# module.net
KiCad netlist of a schematic drawn in EAGLE
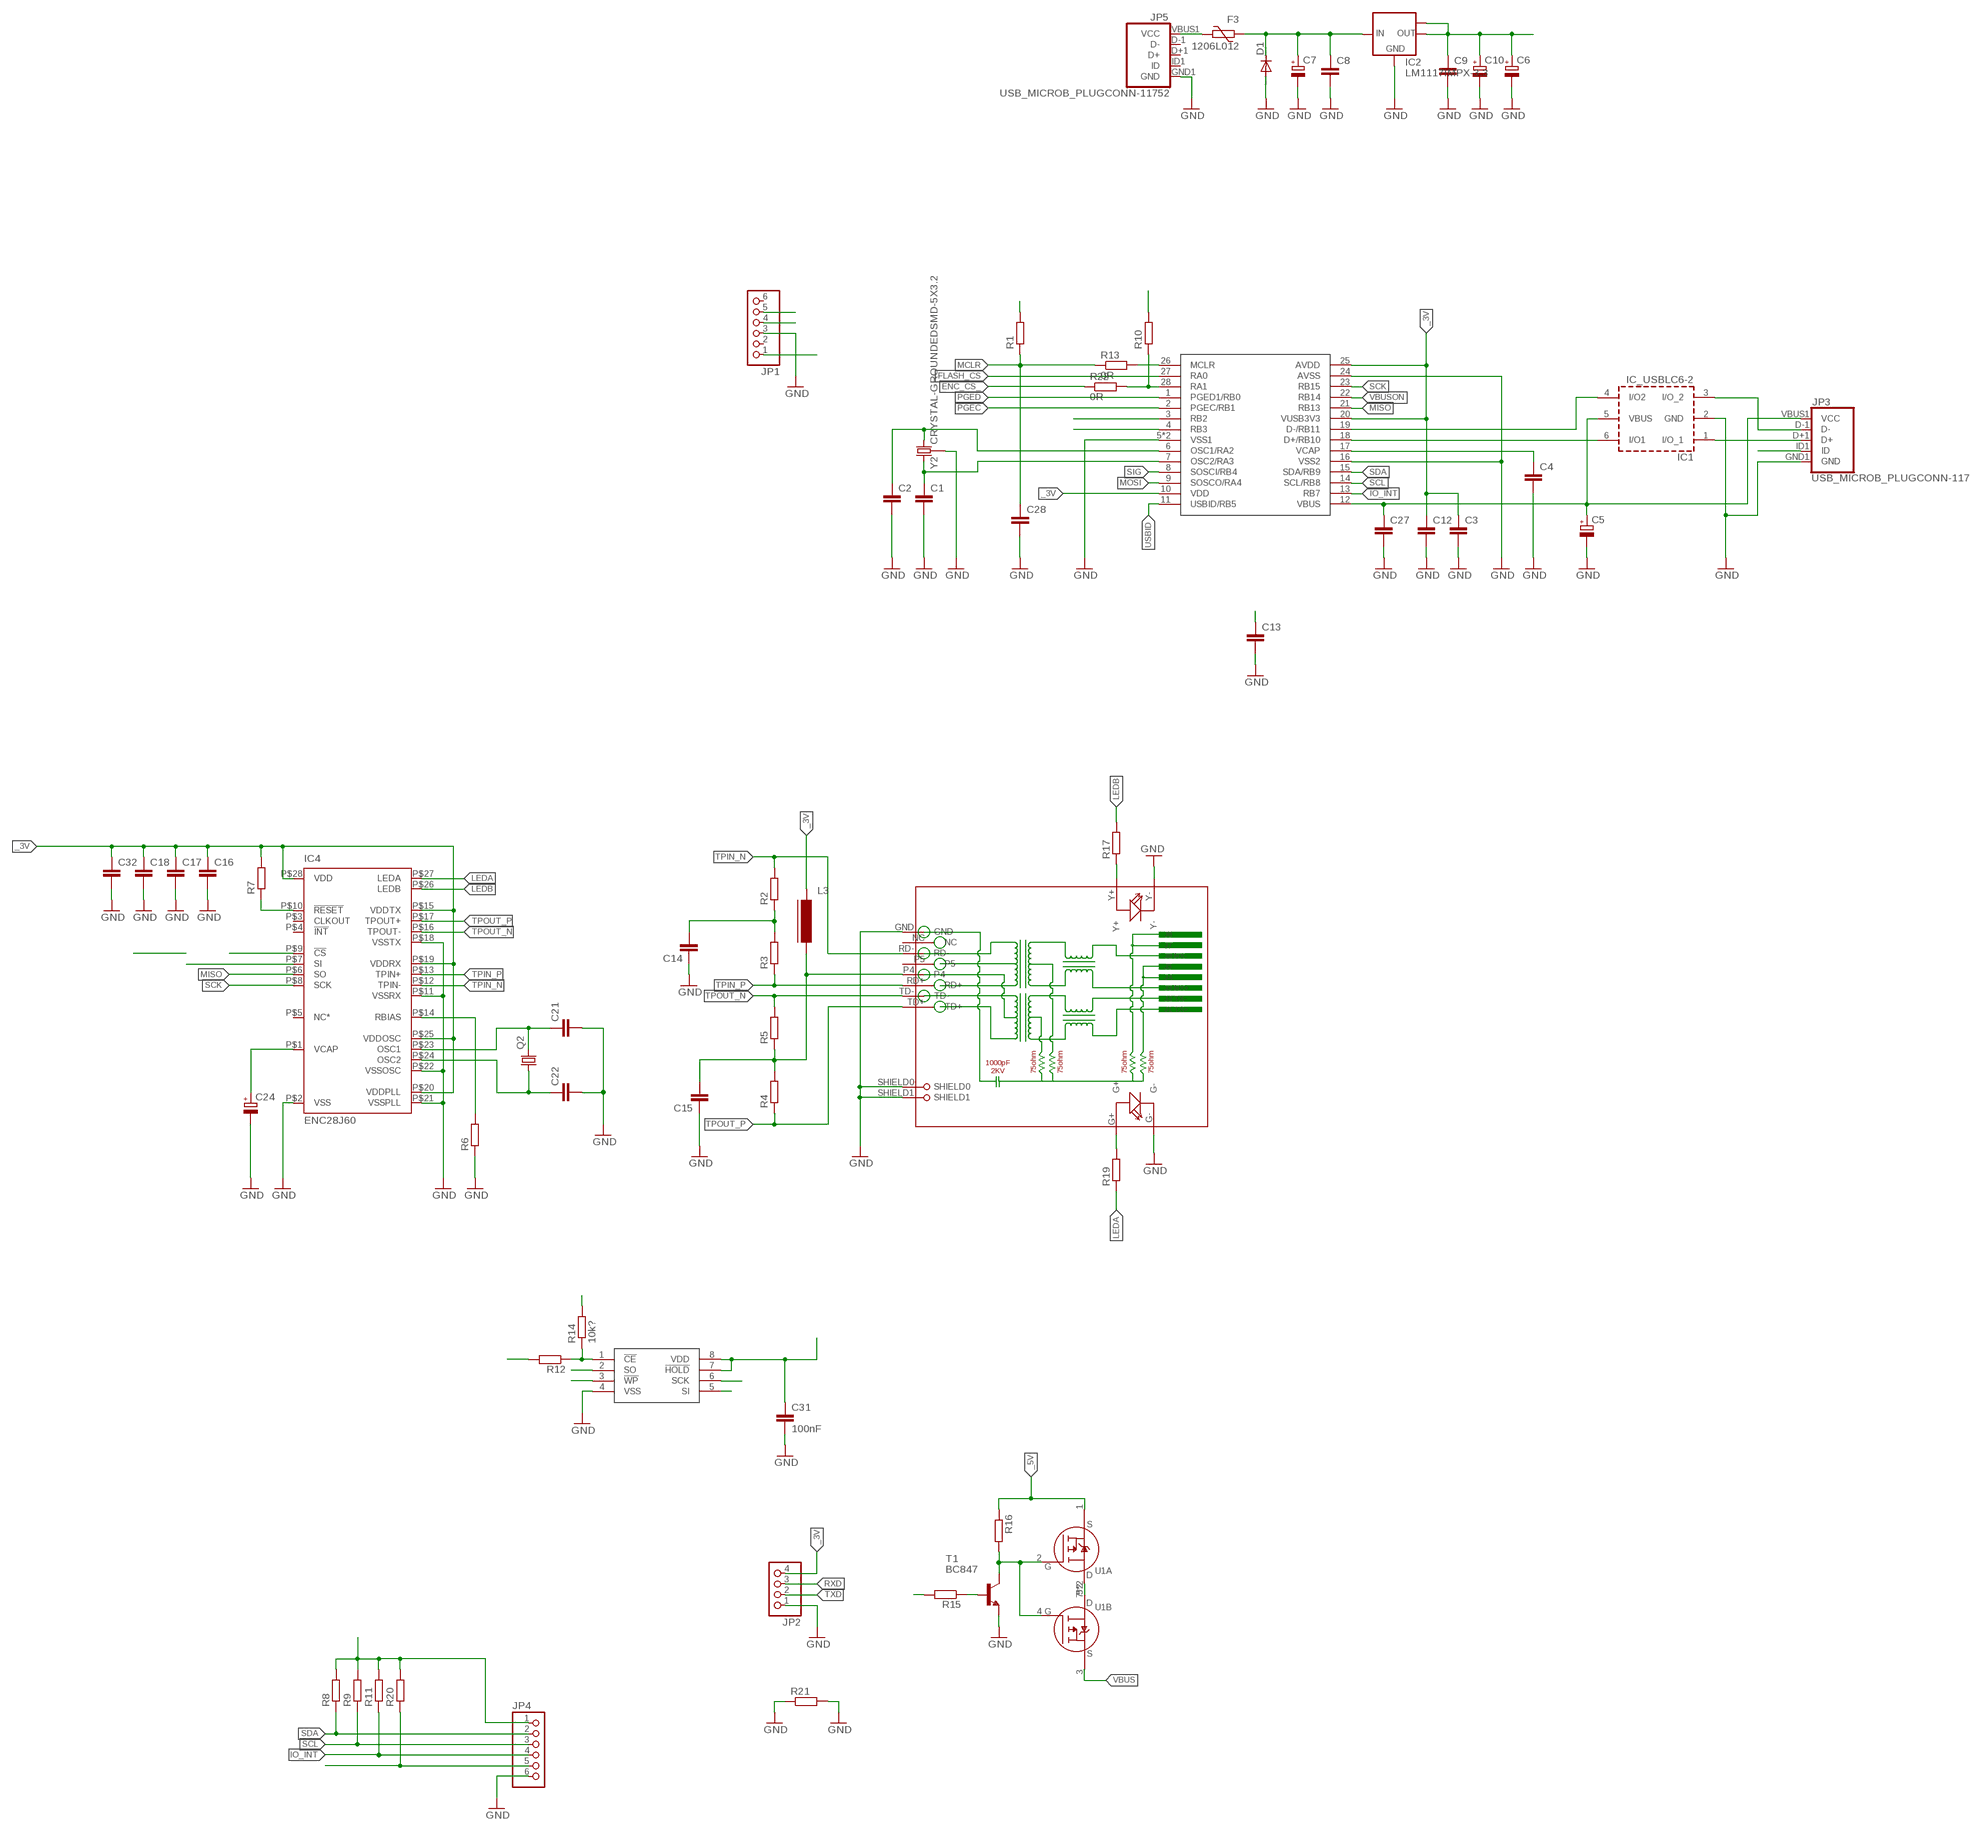
[diagram p0: schematic, sheet 1]

(export (version "E")
  (design (tool "Eeschema 10.0.6"))
  (components
    (comp (ref "C1")
      (value "C-EUC0603")
      (footprint "eagle-import:C0603")
      (libsource (lib "eagle-import") (part "C-EUC0603"))
    )
    (comp (ref "C2")
      (value "C-EUC0603")
      (footprint "eagle-import:C0603")
      (libsource (lib "eagle-import") (part "C-EUC0603"))
    )
    (comp (ref "C3")
      (value "C-EUC0402")
      (footprint "eagle-import:C0402")
      (libsource (lib "eagle-import") (part "C-EUC0402"))
    )
    (comp (ref "C4")
      (value "C-EUC0603")
      (footprint "eagle-import:C0603")
      (libsource (lib "eagle-import") (part "C-EUC0603"))
    )
    (comp (ref "C5")
      (value "CPOL-EUSMCA")
      (footprint "eagle-import:SMC_A")
      (libsource (lib "eagle-import") (part "CPOL-EUSMCA"))
    )
    (comp (ref "C6")
      (value "CPOL-EUSMCA")
      (footprint "eagle-import:SMC_A")
      (libsource (lib "eagle-import") (part "CPOL-EUSMCA"))
    )
    (comp (ref "C7")
      (value "CPOL-EUSMCC")
      (footprint "eagle-import:SMC_C")
      (libsource (lib "eagle-import") (part "CPOL-EUSMCC"))
    )
    (comp (ref "C8")
      (value "C-EUC0603")
      (footprint "eagle-import:C0603")
      (libsource (lib "eagle-import") (part "C-EUC0603"))
    )
    (comp (ref "C9")
      (value "C-EUC0603")
      (footprint "eagle-import:C0603")
      (libsource (lib "eagle-import") (part "C-EUC0603"))
    )
    (comp (ref "C10")
      (value "CPOL-EUSMCB")
      (footprint "eagle-import:SMC_B")
      (libsource (lib "eagle-import") (part "CPOL-EUSMCB"))
    )
    (comp (ref "C12")
      (value "C-EUC0603")
      (footprint "eagle-import:C0603")
      (libsource (lib "eagle-import") (part "C-EUC0603"))
    )
    (comp (ref "C13")
      (value "C-EUC0603")
      (footprint "eagle-import:C0603")
      (libsource (lib "eagle-import") (part "C-EUC0603"))
    )
    (comp (ref "C14")
      (value "C-EUC0603")
      (footprint "eagle-import:C0603")
      (libsource (lib "eagle-import") (part "C-EUC0603"))
    )
    (comp (ref "C15")
      (value "C-EUC0603")
      (footprint "eagle-import:C0603")
      (libsource (lib "eagle-import") (part "C-EUC0603"))
    )
    (comp (ref "C16")
      (value "C-EUC0402")
      (footprint "eagle-import:C0402")
      (libsource (lib "eagle-import") (part "C-EUC0402"))
    )
    (comp (ref "C17")
      (value "C-EUC0402")
      (footprint "eagle-import:C0402")
      (libsource (lib "eagle-import") (part "C-EUC0402"))
    )
    (comp (ref "C18")
      (value "C-EUC0402")
      (footprint "eagle-import:C0402")
      (libsource (lib "eagle-import") (part "C-EUC0402"))
    )
    (comp (ref "C21")
      (value "C-EUC0603")
      (footprint "eagle-import:C0603")
      (libsource (lib "eagle-import") (part "C-EUC0603"))
    )
    (comp (ref "C22")
      (value "C-EUC0603")
      (footprint "eagle-import:C0603")
      (libsource (lib "eagle-import") (part "C-EUC0603"))
    )
    (comp (ref "C24")
      (value "CPOL-EUSMCA")
      (footprint "eagle-import:SMC_A")
      (libsource (lib "eagle-import") (part "CPOL-EUSMCA"))
    )
    (comp (ref "C27")
      (value "C-EUC0603")
      (footprint "eagle-import:C0603")
      (libsource (lib "eagle-import") (part "C-EUC0603"))
    )
    (comp (ref "C28")
      (value "C-EUC0603")
      (footprint "eagle-import:C0603")
      (libsource (lib "eagle-import") (part "C-EUC0603"))
    )
    (comp (ref "C31")
      (value "100nF")
      (footprint "eagle-import:C0603")
      (libsource (lib "eagle-import") (part "C-EUC0603"))
    )
    (comp (ref "C32")
      (value "C-EUC0402")
      (footprint "eagle-import:C0402")
      (libsource (lib "eagle-import") (part "C-EUC0402"))
    )
    (comp (ref "D1")
      (value "DIODE-SMB")
      (footprint "eagle-import:SMB")
      (libsource (lib "eagle-import") (part "DIODE-SMB"))
    )
    (comp (ref "F3")
      (value "1206L012")
      (footprint "eagle-import:1206L")
      (fields (field (name "MF") "Littelfuse"))
      (libsource (lib "eagle-import") (part "?1206L012"))
    )
    (comp (ref "IC1")
      (value "IC_USBLC6-2")
      (footprint "eagle-import:SOT-23-6L")
      (libsource (lib "eagle-import") (part "IC_USBLC6-2"))
    )
    (comp (ref "IC2")
      (value "LM1117IMPX-3.3")
      (footprint "eagle-import:SOT223")
      (libsource (lib "eagle-import") (part "LM1117IMPX-3.3"))
    )
    (comp (ref "IC4")
      (value "ENC28J60")
      (footprint "eagle-import:TSSOP28W")
      (libsource (lib "eagle-import") (part "ENC28J60"))
    )
    (comp (ref "JP1")
      (value "PINHD-1X6")
      (footprint "eagle-import:1X06")
      (libsource (lib "eagle-import") (part "PINHD-1X6"))
    )
    (comp (ref "JP2")
      (value "PINHD-1X4")
      (footprint "eagle-import:1X04")
      (libsource (lib "eagle-import") (part "PINHD-1X4"))
    )
    (comp (ref "JP3")
      (value "USB_MICROB_PLUGCONN-11752")
      (footprint "eagle-import:USB-B-MICRO-SMD_V03")
      (libsource (lib "eagle-import") (part "USB_MICROB_PLUGCONN-11752"))
    )
    (comp (ref "JP4")
      (value "PINHD-1X6")
      (footprint "eagle-import:1X06")
      (libsource (lib "eagle-import") (part "PINHD-1X6"))
    )
    (comp (ref "JP5")
      (value "USB_MICROB_PLUGCONN-11752")
      (footprint "eagle-import:USB-B-MICRO-SMD_V03")
      (libsource (lib "eagle-import") (part "USB_MICROB_PLUGCONN-11752"))
    )
    (comp (ref "L3")
      (value "FERRITE-0805")
      (footprint "eagle-import:FB805")
      (libsource (lib "eagle-import") (part "FERRITE-0805"))
    )
    (comp (ref "Q2")
      (value "CRYSTALHC49S")
      (footprint "eagle-import:HC49_S")
      (libsource (lib "eagle-import") (part "CRYSTALHC49S"))
    )
    (comp (ref "R1")
      (value "R-EU_R0603")
      (footprint "eagle-import:R0603")
      (libsource (lib "eagle-import") (part "R-EU_R0603"))
    )
    (comp (ref "R2")
      (value "R-EU_R0603")
      (footprint "eagle-import:R0603")
      (libsource (lib "eagle-import") (part "R-EU_R0603"))
    )
    (comp (ref "R3")
      (value "R-EU_R0603")
      (footprint "eagle-import:R0603")
      (libsource (lib "eagle-import") (part "R-EU_R0603"))
    )
    (comp (ref "R4")
      (value "R-EU_R0603")
      (footprint "eagle-import:R0603")
      (libsource (lib "eagle-import") (part "R-EU_R0603"))
    )
    (comp (ref "R5")
      (value "R-EU_R0603")
      (footprint "eagle-import:R0603")
      (libsource (lib "eagle-import") (part "R-EU_R0603"))
    )
    (comp (ref "R6")
      (value "R-EU_R0805")
      (footprint "eagle-import:R0805")
      (libsource (lib "eagle-import") (part "R-EU_R0805"))
    )
    (comp (ref "R7")
      (value "R-EU_R0603")
      (footprint "eagle-import:R0603")
      (libsource (lib "eagle-import") (part "R-EU_R0603"))
    )
    (comp (ref "R8")
      (value "R-EU_R0603")
      (footprint "eagle-import:R0603")
      (libsource (lib "eagle-import") (part "R-EU_R0603"))
    )
    (comp (ref "R9")
      (value "R-EU_R0603")
      (footprint "eagle-import:R0603")
      (libsource (lib "eagle-import") (part "R-EU_R0603"))
    )
    (comp (ref "R10")
      (value "R-EU_R0603")
      (footprint "eagle-import:R0603")
      (libsource (lib "eagle-import") (part "R-EU_R0603"))
    )
    (comp (ref "R11")
      (value "R-EU_R0603")
      (footprint "eagle-import:R0603")
      (libsource (lib "eagle-import") (part "R-EU_R0603"))
    )
    (comp (ref "R12")
      (value "R-EU_R0603")
      (footprint "eagle-import:R0603")
      (libsource (lib "eagle-import") (part "R-EU_R0603"))
    )
    (comp (ref "R13")
      (value "0R")
      (footprint "eagle-import:R0603")
      (libsource (lib "eagle-import") (part "R-EU_R0603"))
    )
    (comp (ref "R14")
      (value "10k?")
      (footprint "eagle-import:R0603")
      (libsource (lib "eagle-import") (part "R-EU_R0603"))
    )
    (comp (ref "R15")
      (value "R-EU_R0603")
      (footprint "eagle-import:R0603")
      (libsource (lib "eagle-import") (part "R-EU_R0603"))
    )
    (comp (ref "R16")
      (value "R-EU_R0402")
      (footprint "eagle-import:R0402")
      (libsource (lib "eagle-import") (part "R-EU_R0402"))
    )
    (comp (ref "R17")
      (value "R-EU_R1206")
      (footprint "eagle-import:R1206")
      (libsource (lib "eagle-import") (part "R-EU_R1206"))
    )
    (comp (ref "R19")
      (value "R-EU_R1206")
      (footprint "eagle-import:R1206")
      (libsource (lib "eagle-import") (part "R-EU_R1206"))
    )
    (comp (ref "R20")
      (value "R-EU_R0603")
      (footprint "eagle-import:R0603")
      (libsource (lib "eagle-import") (part "R-EU_R0603"))
    )
    (comp (ref "R21")
      (value "R-EU_R1206")
      (footprint "eagle-import:R1206")
      (libsource (lib "eagle-import") (part "R-EU_R1206"))
    )
    (comp (ref "R22")
      (value "0R")
      (footprint "eagle-import:R0603")
      (libsource (lib "eagle-import") (part "R-EU_R0603"))
    )
    (comp (ref "RJ1")
      (value "HR911105A")
      (footprint "eagle-import:HR911105A")
      (libsource (lib "eagle-import") (part "HR911105A"))
    )
    (comp (ref "T1")
      (value "BC847")
      (footprint "eagle-import:SOT23")
      (libsource (lib "eagle-import") (part "BC847"))
    )
    (comp (ref "U$1")
      (value "PIC32MX250F128B")
      (footprint "eagle-import:QFN-S28-6X6")
      (libsource (lib "eagle-import") (part "PIC32MX250F128B"))
    )
    (comp (ref "U$2")
      (value "SST25VF016BSO8M")
      (footprint "eagle-import:SO-08M")
      (libsource (lib "eagle-import") (part "SST25VF016BSO8M"))
    )
    (comp (ref "U1")
      (value "IRF7314_P_MOSFET")
      (footprint "eagle-import:SO-8")
      (libsource (lib "eagle-import") (part "IRF7314_P_MOSFET"))
    )
    (comp (ref "Y2")
      (value "CRYSTAL-GROUNDEDSMD-5X3.2")
      (footprint "eagle-import:CRYSTAL-SMD-5X3.2-4PAD")
      (libsource (lib "eagle-import") (part "CRYSTAL-GROUNDEDSMD-5X3.2"))
    )
  )
  (nets
    (net (code "1") (name "ENC_CS_") (class "Default")
      (node (ref "IC4") (pin "P$9") (pinfunction "~{CS}_P$9") (pintype "input"))
      (node (ref "R22") (pin "1") (pinfunction "1_1") (pintype "passive"))
    )
    (net (code "2") (name "FLASH_CS") (class "Default")
      (node (ref "R12") (pin "2") (pinfunction "2_2") (pintype "passive"))
      (node (ref "U$1") (pin "27") (pinfunction "RA0_27") (pintype "bidirectional"))
    )
    (net (code "3") (name "GND") (class "Default")
      (node (ref "C1") (pin "2") (pinfunction "2_2") (pintype "passive"))
      (node (ref "C10") (pin "-") (pinfunction "-_-") (pintype "passive"))
      (node (ref "C12") (pin "2") (pinfunction "2_2") (pintype "passive"))
      (node (ref "C13") (pin "2") (pinfunction "2_2") (pintype "passive"))
      (node (ref "C14") (pin "1") (pinfunction "1_1") (pintype "passive"))
      (node (ref "C15") (pin "1") (pinfunction "1_1") (pintype "passive"))
      (node (ref "C16") (pin "2") (pinfunction "2_2") (pintype "passive"))
      (node (ref "C17") (pin "2") (pinfunction "2_2") (pintype "passive"))
      (node (ref "C18") (pin "2") (pinfunction "2_2") (pintype "passive"))
      (node (ref "C2") (pin "2") (pinfunction "2_2") (pintype "passive"))
      (node (ref "C21") (pin "2") (pinfunction "2_2") (pintype "passive"))
      (node (ref "C22") (pin "2") (pinfunction "2_2") (pintype "passive"))
      (node (ref "C24") (pin "-") (pinfunction "-_-") (pintype "passive"))
      (node (ref "C27") (pin "2") (pinfunction "2_2") (pintype "passive"))
      (node (ref "C28") (pin "2") (pinfunction "2_2") (pintype "passive"))
      (node (ref "C3") (pin "2") (pinfunction "2_2") (pintype "passive"))
      (node (ref "C31") (pin "2") (pinfunction "2_2") (pintype "passive"))
      (node (ref "C32") (pin "2") (pinfunction "2_2") (pintype "passive"))
      (node (ref "C4") (pin "2") (pinfunction "2_2") (pintype "passive"))
      (node (ref "C5") (pin "-") (pinfunction "-_-") (pintype "passive"))
      (node (ref "C6") (pin "-") (pinfunction "-_-") (pintype "passive"))
      (node (ref "C7") (pin "-") (pinfunction "-_-") (pintype "passive"))
      (node (ref "C8") (pin "2") (pinfunction "2_2") (pintype "passive"))
      (node (ref "C9") (pin "2") (pinfunction "2_2") (pintype "passive"))
      (node (ref "D1") (pin "A") (pinfunction "A_A") (pintype "passive"))
      (node (ref "IC1") (pin "2") (pinfunction "GND_2") (pintype "bidirectional"))
      (node (ref "IC2") (pin "1") (pinfunction "GND_1") (pintype "input"))
      (node (ref "IC4") (pin "P$11") (pinfunction "VSSRX_P$11") (pintype "input"))
      (node (ref "IC4") (pin "P$18") (pinfunction "VSSTX_P$18") (pintype "input"))
      (node (ref "IC4") (pin "P$2") (pinfunction "VSS_P$2") (pintype "input"))
      (node (ref "IC4") (pin "P$21") (pinfunction "VSSPLL_P$21") (pintype "input"))
      (node (ref "IC4") (pin "P$22") (pinfunction "VSSOSC_P$22") (pintype "input"))
      (node (ref "JP1") (pin "3") (pinfunction "3_3") (pintype "passive"))
      (node (ref "JP2") (pin "1") (pinfunction "1_1") (pintype "passive"))
      (node (ref "JP3") (pin "GND1") (pinfunction "GND_GND1") (pintype "bidirectional"))
      (node (ref "JP4") (pin "6") (pinfunction "6_6") (pintype "passive"))
      (node (ref "JP5") (pin "GND1") (pinfunction "GND_GND1") (pintype "bidirectional"))
      (node (ref "R21") (pin "1") (pinfunction "1_1") (pintype "passive"))
      (node (ref "R21") (pin "2") (pinfunction "2_2") (pintype "passive"))
      (node (ref "R6") (pin "1") (pinfunction "1_1") (pintype "passive"))
      (node (ref "RJ1") (pin "G-") (pinfunction "G-_G-") (pintype "bidirectional"))
      (node (ref "RJ1") (pin "GND") (pinfunction "GND_GND") (pintype "bidirectional"))
      (node (ref "RJ1") (pin "SHIELD0") (pinfunction "SHIELD0_SHIELD0") (pintype "bidirectional"))
      (node (ref "RJ1") (pin "SHIELD1") (pinfunction "SHIELD1_SHIELD1") (pintype "bidirectional"))
      (node (ref "RJ1") (pin "Y-") (pinfunction "Y-_Y-") (pintype "bidirectional"))
      (node (ref "T1") (pin "2") (pinfunction "E_2") (pintype "passive"))
      (node (ref "U$1") (pin "16") (pinfunction "VSS2_16") (pintype "bidirectional"))
      (node (ref "U$1") (pin "24") (pinfunction "AVSS_24") (pintype "bidirectional"))
      (node (ref "U$1") (pin "5") (pinfunction "VSS1_5") (pintype "bidirectional"))
      (node (ref "U$1") (pin "EXP") (pinfunction "VSS1_EXP") (pintype "bidirectional"))
      (node (ref "U$2") (pin "4") (pinfunction "VSS_4") (pintype "bidirectional"))
      (node (ref "Y2") (pin "2") (pinfunction "3_2") (pintype "passive"))
      (node (ref "Y2") (pin "4") (pinfunction "3_4") (pintype "passive"))
    )
    (net (code "4") (name "IO_INT") (class "Default")
      (node (ref "JP4") (pin "4") (pinfunction "4_4") (pintype "passive"))
      (node (ref "R11") (pin "1") (pinfunction "1_1") (pintype "passive"))
      (node (ref "U$1") (pin "13") (pinfunction "RB7_13") (pintype "bidirectional"))
    )
    (net (code "5") (name "LEDA") (class "Default")
      (node (ref "IC4") (pin "P$27") (pinfunction "LEDA_P$27") (pintype "output"))
      (node (ref "R19") (pin "1") (pinfunction "1_1") (pintype "passive"))
    )
    (net (code "6") (name "LEDB") (class "Default")
      (node (ref "IC4") (pin "P$26") (pinfunction "LEDB_P$26") (pintype "output"))
      (node (ref "R17") (pin "2") (pinfunction "2_2") (pintype "passive"))
    )
    (net (code "7") (name "MCLR") (class "Default")
      (node (ref "C28") (pin "1") (pinfunction "1_1") (pintype "passive"))
      (node (ref "JP1") (pin "1") (pinfunction "1_1") (pintype "passive"))
      (node (ref "R1") (pin "1") (pinfunction "1_1") (pintype "passive"))
      (node (ref "R13") (pin "1") (pinfunction "1_1") (pintype "passive"))
    )
    (net (code "8") (name "MISO") (class "Default")
      (node (ref "IC4") (pin "P$6") (pinfunction "SO_P$6") (pintype "output"))
      (node (ref "U$1") (pin "21") (pinfunction "RB13_21") (pintype "bidirectional"))
      (node (ref "U$2") (pin "2") (pinfunction "SO_2") (pintype "bidirectional"))
    )
    (net (code "9") (name "MOSI") (class "Default")
      (node (ref "IC4") (pin "P$7") (pinfunction "SI_P$7") (pintype "input"))
      (node (ref "U$1") (pin "9") (pinfunction "SOSCO/RA4_9") (pintype "bidirectional"))
      (node (ref "U$2") (pin "5") (pinfunction "SI_5") (pintype "bidirectional"))
    )
    (net (code "10") (name "Net-(C14-Pad2)") (class "Default")
      (node (ref "C14") (pin "2") (pinfunction "2_2") (pintype "passive"))
      (node (ref "R2") (pin "1") (pinfunction "1_1") (pintype "passive"))
      (node (ref "R3") (pin "2") (pinfunction "2_2") (pintype "passive"))
    )
    (net (code "11") (name "Net-(C15-Pad2)") (class "Default")
      (node (ref "C15") (pin "2") (pinfunction "2_2") (pintype "passive"))
      (node (ref "L3") (pin "2") (pinfunction "2_2") (pintype "passive"))
      (node (ref "R4") (pin "2") (pinfunction "2_2") (pintype "passive"))
      (node (ref "R5") (pin "1") (pinfunction "1_1") (pintype "passive"))
      (node (ref "RJ1") (pin "P4") (pinfunction "P4_P4") (pintype "bidirectional"))
    )
    (net (code "12") (name "Net-(IC1-I{slash}O1)") (class "Default")
      (node (ref "IC1") (pin "6") (pinfunction "I/O1_6") (pintype "bidirectional"))
      (node (ref "U$1") (pin "18") (pinfunction "D+/RB10_18") (pintype "bidirectional"))
    )
    (net (code "13") (name "Net-(IC1-I{slash}O2)") (class "Default")
      (node (ref "IC1") (pin "4") (pinfunction "I/O2_4") (pintype "bidirectional"))
      (node (ref "U$1") (pin "19") (pinfunction "D-/RB11_19") (pintype "bidirectional"))
    )
    (net (code "14") (name "Net-(IC1-I{slash}O_1)") (class "Default")
      (node (ref "IC1") (pin "1") (pinfunction "I/O_1_1") (pintype "bidirectional"))
      (node (ref "JP3") (pin "D+1") (pinfunction "D+_D+1") (pintype "bidirectional"))
    )
    (net (code "15") (name "Net-(IC1-I{slash}O_2)") (class "Default")
      (node (ref "IC1") (pin "3") (pinfunction "I/O_2_3") (pintype "bidirectional"))
      (node (ref "JP3") (pin "D-1") (pinfunction "D-_D-1") (pintype "bidirectional"))
    )
    (net (code "16") (name "Net-(IC4-OSC1)") (class "Default")
      (node (ref "C21") (pin "1") (pinfunction "1_1") (pintype "passive"))
      (node (ref "IC4") (pin "P$23") (pinfunction "OSC1_P$23") (pintype "input"))
      (node (ref "Q2") (pin "2") (pinfunction "2_2") (pintype "passive"))
    )
    (net (code "17") (name "Net-(IC4-OSC2)") (class "Default")
      (node (ref "C22") (pin "1") (pinfunction "1_1") (pintype "passive"))
      (node (ref "IC4") (pin "P$24") (pinfunction "OSC2_P$24") (pintype "output"))
      (node (ref "Q2") (pin "1") (pinfunction "1_1") (pintype "passive"))
    )
    (net (code "18") (name "Net-(IC4-RBIAS)") (class "Default")
      (node (ref "IC4") (pin "P$14") (pinfunction "RBIAS_P$14") (pintype "input"))
      (node (ref "R6") (pin "2") (pinfunction "2_2") (pintype "passive"))
    )
    (net (code "19") (name "Net-(IC4-VCAP)") (class "Default")
      (node (ref "C24") (pin "+") (pinfunction "+_+") (pintype "passive"))
      (node (ref "IC4") (pin "P$1") (pinfunction "VCAP_P$1") (pintype "input"))
    )
    (net (code "20") (name "Net-(IC4-~{RESET})") (class "Default")
      (node (ref "IC4") (pin "P$10") (pinfunction "~{RESET}_P$10") (pintype "input"))
      (node (ref "R7") (pin "1") (pinfunction "1_1") (pintype "passive"))
    )
    (net (code "21") (name "Net-(JP5-VCC)") (class "Default")
      (node (ref "F3") (pin "1") (pinfunction "1_1") (pintype "passive"))
      (node (ref "JP5") (pin "VBUS1") (pinfunction "VCC_VBUS1") (pintype "bidirectional"))
    )
    (net (code "22") (name "Net-(R17-Pad1)") (class "Default")
      (node (ref "R17") (pin "1") (pinfunction "1_1") (pintype "passive"))
      (node (ref "RJ1") (pin "Y+") (pinfunction "Y+_Y+") (pintype "bidirectional"))
    )
    (net (code "23") (name "Net-(R19-Pad2)") (class "Default")
      (node (ref "R19") (pin "2") (pinfunction "2_2") (pintype "passive"))
      (node (ref "RJ1") (pin "G+") (pinfunction "G+_G+") (pintype "bidirectional"))
    )
    (net (code "24") (name "Net-(T1-B)") (class "Default")
      (node (ref "R15") (pin "1") (pinfunction "1_1") (pintype "passive"))
      (node (ref "T1") (pin "1") (pinfunction "B_1") (pintype "passive"))
    )
    (net (code "25") (name "Net-(T1-C)") (class "Default")
      (node (ref "R16") (pin "2") (pinfunction "2_2") (pintype "passive"))
      (node (ref "T1") (pin "3") (pinfunction "C_3") (pintype "passive"))
      (node (ref "U1") (pin "2") (pinfunction "G_2") (pintype "bidirectional"))
      (node (ref "U1") (pin "4") (pinfunction "G_4") (pintype "bidirectional"))
    )
    (net (code "26") (name "Net-(U$1-MCLR)") (class "Default")
      (node (ref "R13") (pin "2") (pinfunction "2_2") (pintype "passive"))
      (node (ref "U$1") (pin "26") (pinfunction "MCLR_26") (pintype "bidirectional"))
    )
    (net (code "27") (name "Net-(U$1-OSC1{slash}RA2)") (class "Default")
      (node (ref "C2") (pin "1") (pinfunction "1_1") (pintype "passive"))
      (node (ref "U$1") (pin "6") (pinfunction "OSC1/RA2_6") (pintype "bidirectional"))
      (node (ref "Y2") (pin "1") (pinfunction "2_1") (pintype "passive"))
    )
    (net (code "28") (name "Net-(U$1-OSC2{slash}RA3)") (class "Default")
      (node (ref "C1") (pin "1") (pinfunction "1_1") (pintype "passive"))
      (node (ref "U$1") (pin "7") (pinfunction "OSC2/RA3_7") (pintype "bidirectional"))
      (node (ref "Y2") (pin "3") (pinfunction "1_3") (pintype "passive"))
    )
    (net (code "29") (name "Net-(U$1-RA1)") (class "Default")
      (node (ref "R10") (pin "1") (pinfunction "1_1") (pintype "passive"))
      (node (ref "R22") (pin "2") (pinfunction "2_2") (pintype "passive"))
      (node (ref "U$1") (pin "28") (pinfunction "RA1_28") (pintype "bidirectional"))
    )
    (net (code "30") (name "Net-(U$1-VCAP)") (class "Default")
      (node (ref "C4") (pin "1") (pinfunction "1_1") (pintype "passive"))
      (node (ref "U$1") (pin "17") (pinfunction "VCAP_17") (pintype "bidirectional"))
    )
    (net (code "31") (name "Net-(U$2-~{CE})") (class "Default")
      (node (ref "R12") (pin "1") (pinfunction "1_1") (pintype "passive"))
      (node (ref "R14") (pin "1") (pinfunction "1_1") (pintype "passive"))
      (node (ref "U$2") (pin "1") (pinfunction "~{CE}_1") (pintype "bidirectional"))
    )
    (net (code "32") (name "Net-(U1A-D-Pad7)") (class "Default")
      (node (ref "U1") (pin "5") (pinfunction "D_5") (pintype "bidirectional"))
      (node (ref "U1") (pin "6") (pinfunction "D_6") (pintype "bidirectional"))
      (node (ref "U1") (pin "7") (pinfunction "D_7") (pintype "bidirectional"))
      (node (ref "U1") (pin "8") (pinfunction "D_8") (pintype "bidirectional"))
    )
    (net (code "33") (name "PGEC") (class "Default")
      (node (ref "JP1") (pin "5") (pinfunction "5_5") (pintype "passive"))
      (node (ref "U$1") (pin "2") (pinfunction "PGEC/RB1_2") (pintype "bidirectional"))
    )
    (net (code "34") (name "PGED") (class "Default")
      (node (ref "JP1") (pin "4") (pinfunction "4_4") (pintype "passive"))
      (node (ref "U$1") (pin "1") (pinfunction "PGED1/RB0_1") (pintype "bidirectional"))
    )
    (net (code "35") (name "RXD") (class "Default")
      (node (ref "JP2") (pin "3") (pinfunction "3_3") (pintype "passive"))
      (node (ref "U$1") (pin "3") (pinfunction "RB2_3") (pintype "bidirectional"))
    )
    (net (code "36") (name "SCK") (class "Default")
      (node (ref "IC4") (pin "P$8") (pinfunction "SCK_P$8") (pintype "input"))
      (node (ref "U$1") (pin "23") (pinfunction "RB15_23") (pintype "bidirectional"))
      (node (ref "U$2") (pin "6") (pinfunction "SCK_6") (pintype "bidirectional"))
    )
    (net (code "37") (name "SCL") (class "Default")
      (node (ref "JP4") (pin "3") (pinfunction "3_3") (pintype "passive"))
      (node (ref "R9") (pin "1") (pinfunction "1_1") (pintype "passive"))
      (node (ref "U$1") (pin "14") (pinfunction "SCL/RB8_14") (pintype "bidirectional"))
    )
    (net (code "38") (name "SDA") (class "Default")
      (node (ref "JP4") (pin "2") (pinfunction "2_2") (pintype "passive"))
      (node (ref "R8") (pin "1") (pinfunction "1_1") (pintype "passive"))
      (node (ref "U$1") (pin "15") (pinfunction "SDA/RB9_15") (pintype "bidirectional"))
    )
    (net (code "39") (name "SIG") (class "Default")
      (node (ref "JP4") (pin "5") (pinfunction "5_5") (pintype "passive"))
      (node (ref "R20") (pin "1") (pinfunction "1_1") (pintype "passive"))
      (node (ref "U$1") (pin "8") (pinfunction "SOSCI/RB4_8") (pintype "bidirectional"))
    )
    (net (code "40") (name "TPIN_N") (class "Default")
      (node (ref "IC4") (pin "P$12") (pinfunction "TPIN-_P$12") (pintype "input"))
      (node (ref "R2") (pin "2") (pinfunction "2_2") (pintype "passive"))
      (node (ref "RJ1") (pin "RD-") (pinfunction "RD-_RD-") (pintype "bidirectional"))
    )
    (net (code "41") (name "TPIN_P") (class "Default")
      (node (ref "IC4") (pin "P$13") (pinfunction "TPIN+_P$13") (pintype "input"))
      (node (ref "R3") (pin "1") (pinfunction "1_1") (pintype "passive"))
      (node (ref "RJ1") (pin "RD+") (pinfunction "RD+_RD+") (pintype "bidirectional"))
    )
    (net (code "42") (name "TPOUT_N") (class "Default")
      (node (ref "IC4") (pin "P$16") (pinfunction "TPOUT-_P$16") (pintype "output"))
      (node (ref "R5") (pin "2") (pinfunction "2_2") (pintype "passive"))
      (node (ref "RJ1") (pin "TD-") (pinfunction "TD-_TD-") (pintype "bidirectional"))
    )
    (net (code "43") (name "TPOUT_P") (class "Default")
      (node (ref "IC4") (pin "P$17") (pinfunction "TPOUT+_P$17") (pintype "output"))
      (node (ref "R4") (pin "1") (pinfunction "1_1") (pintype "passive"))
      (node (ref "RJ1") (pin "TD+") (pinfunction "TD+_TD+") (pintype "bidirectional"))
    )
    (net (code "44") (name "TXD") (class "Default")
      (node (ref "JP2") (pin "2") (pinfunction "2_2") (pintype "passive"))
      (node (ref "U$1") (pin "4") (pinfunction "RB3_4") (pintype "bidirectional"))
    )
    (net (code "45") (name "USBID") (class "Default")
      (node (ref "JP3") (pin "ID1") (pinfunction "ID_ID1") (pintype "bidirectional"))
      (node (ref "U$1") (pin "11") (pinfunction "USBID/RB5_11") (pintype "bidirectional"))
    )
    (net (code "46") (name "VBUS") (class "Default")
      (node (ref "C27") (pin "1") (pinfunction "1_1") (pintype "passive"))
      (node (ref "C5") (pin "+") (pinfunction "+_+") (pintype "passive"))
      (node (ref "IC1") (pin "5") (pinfunction "VBUS_5") (pintype "bidirectional"))
      (node (ref "JP3") (pin "VBUS1") (pinfunction "VCC_VBUS1") (pintype "bidirectional"))
      (node (ref "U$1") (pin "12") (pinfunction "VBUS_12") (pintype "bidirectional"))
      (node (ref "U1") (pin "3") (pinfunction "S_3") (pintype "bidirectional"))
    )
    (net (code "47") (name "VBUSON") (class "Default")
      (node (ref "R15") (pin "2") (pinfunction "2_2") (pintype "passive"))
      (node (ref "U$1") (pin "22") (pinfunction "RB14_22") (pintype "bidirectional"))
    )
    (net (code "48") (name "_3V") (class "Default")
      (node (ref "C10") (pin "+") (pinfunction "+_+") (pintype "passive"))
      (node (ref "C12") (pin "1") (pinfunction "1_1") (pintype "passive"))
      (node (ref "C13") (pin "1") (pinfunction "1_1") (pintype "passive"))
      (node (ref "C16") (pin "1") (pinfunction "1_1") (pintype "passive"))
      (node (ref "C17") (pin "1") (pinfunction "1_1") (pintype "passive"))
      (node (ref "C18") (pin "1") (pinfunction "1_1") (pintype "passive"))
      (node (ref "C3") (pin "1") (pinfunction "1_1") (pintype "passive"))
      (node (ref "C31") (pin "1") (pinfunction "1_1") (pintype "passive"))
      (node (ref "C32") (pin "1") (pinfunction "1_1") (pintype "passive"))
      (node (ref "C6") (pin "+") (pinfunction "+_+") (pintype "passive"))
      (node (ref "C9") (pin "1") (pinfunction "1_1") (pintype "passive"))
      (node (ref "IC2") (pin "2") (pinfunction "OUT_2") (pintype "passive"))
      (node (ref "IC2") (pin "TAB") (pinfunction "OUT1_TAB") (pintype "passive"))
      (node (ref "IC4") (pin "P$15") (pinfunction "VDDTX_P$15") (pintype "input"))
      (node (ref "IC4") (pin "P$19") (pinfunction "VDDRX_P$19") (pintype "input"))
      (node (ref "IC4") (pin "P$20") (pinfunction "VDDPLL_P$20") (pintype "input"))
      (node (ref "IC4") (pin "P$25") (pinfunction "VDDOSC_P$25") (pintype "input"))
      (node (ref "IC4") (pin "P$28") (pinfunction "VDD_P$28") (pintype "input"))
      (node (ref "JP2") (pin "4") (pinfunction "4_4") (pintype "passive"))
      (node (ref "JP4") (pin "1") (pinfunction "1_1") (pintype "passive"))
      (node (ref "L3") (pin "1") (pinfunction "1_1") (pintype "passive"))
      (node (ref "R1") (pin "2") (pinfunction "2_2") (pintype "passive"))
      (node (ref "R10") (pin "2") (pinfunction "2_2") (pintype "passive"))
      (node (ref "R11") (pin "2") (pinfunction "2_2") (pintype "passive"))
      (node (ref "R14") (pin "2") (pinfunction "2_2") (pintype "passive"))
      (node (ref "R20") (pin "2") (pinfunction "2_2") (pintype "passive"))
      (node (ref "R7") (pin "2") (pinfunction "2_2") (pintype "passive"))
      (node (ref "R8") (pin "2") (pinfunction "2_2") (pintype "passive"))
      (node (ref "R9") (pin "2") (pinfunction "2_2") (pintype "passive"))
      (node (ref "U$1") (pin "10") (pinfunction "VDD_10") (pintype "bidirectional"))
      (node (ref "U$1") (pin "20") (pinfunction "VUSB3V3_20") (pintype "bidirectional"))
      (node (ref "U$1") (pin "25") (pinfunction "AVDD_25") (pintype "bidirectional"))
      (node (ref "U$2") (pin "3") (pinfunction "~{WP}_3") (pintype "bidirectional"))
      (node (ref "U$2") (pin "7") (pinfunction "~{HOLD}_7") (pintype "bidirectional"))
      (node (ref "U$2") (pin "8") (pinfunction "VDD_8") (pintype "bidirectional"))
    )
    (net (code "49") (name "_5V") (class "Default")
      (node (ref "C7") (pin "+") (pinfunction "+_+") (pintype "passive"))
      (node (ref "C8") (pin "1") (pinfunction "1_1") (pintype "passive"))
      (node (ref "D1") (pin "C") (pinfunction "C_C") (pintype "passive"))
      (node (ref "F3") (pin "2") (pinfunction "2_2") (pintype "passive"))
      (node (ref "IC2") (pin "3") (pinfunction "IN_3") (pintype "input"))
      (node (ref "R16") (pin "1") (pinfunction "1_1") (pintype "passive"))
      (node (ref "U1") (pin "1") (pinfunction "S_1") (pintype "bidirectional"))
    )
    (net (code "50") (name "unconnected-(IC4-CLKOUT-PadP$3)") (class "Default")
      (node (ref "IC4") (pin "P$3") (pinfunction "CLKOUT_P$3") (pintype "output"))
    )
    (net (code "51") (name "unconnected-(IC4-NC*-PadP$5)") (class "Default")
      (node (ref "IC4") (pin "P$5") (pinfunction "NC*_P$5") (pintype "output"))
    )
    (net (code "52") (name "unconnected-(IC4-~{INT}-PadP$4)") (class "Default")
      (node (ref "IC4") (pin "P$4") (pinfunction "~{INT}_P$4") (pintype "output"))
    )
    (net (code "53") (name "unconnected-(JP1-Pad2)") (class "Default")
      (node (ref "JP1") (pin "2") (pinfunction "2_2") (pintype "passive"))
    )
    (net (code "54") (name "unconnected-(JP1-Pad6)") (class "Default")
      (node (ref "JP1") (pin "6") (pinfunction "6_6") (pintype "passive"))
    )
    (net (code "55") (name "unconnected-(JP5-D+-PadD+1)") (class "Default")
      (node (ref "JP5") (pin "D+1") (pinfunction "D+_D+1") (pintype "bidirectional"))
    )
    (net (code "56") (name "unconnected-(JP5-D--PadD-1)") (class "Default")
      (node (ref "JP5") (pin "D-1") (pinfunction "D-_D-1") (pintype "bidirectional"))
    )
    (net (code "57") (name "unconnected-(JP5-ID-PadID1)") (class "Default")
      (node (ref "JP5") (pin "ID1") (pinfunction "ID_ID1") (pintype "bidirectional"))
    )
    (net (code "58") (name "unconnected-(RJ1-PadNC)") (class "Default")
      (node (ref "RJ1") (pin "NC") (pinfunction "NC_NC") (pintype "bidirectional"))
    )
    (net (code "59") (name "unconnected-(RJ1-PadP5)") (class "Default")
      (node (ref "RJ1") (pin "P5") (pinfunction "P5_P5") (pintype "bidirectional"))
    )
  )
)
